# Power_Supply.net
KiCad netlist of a schematic drawn in Altium Designer
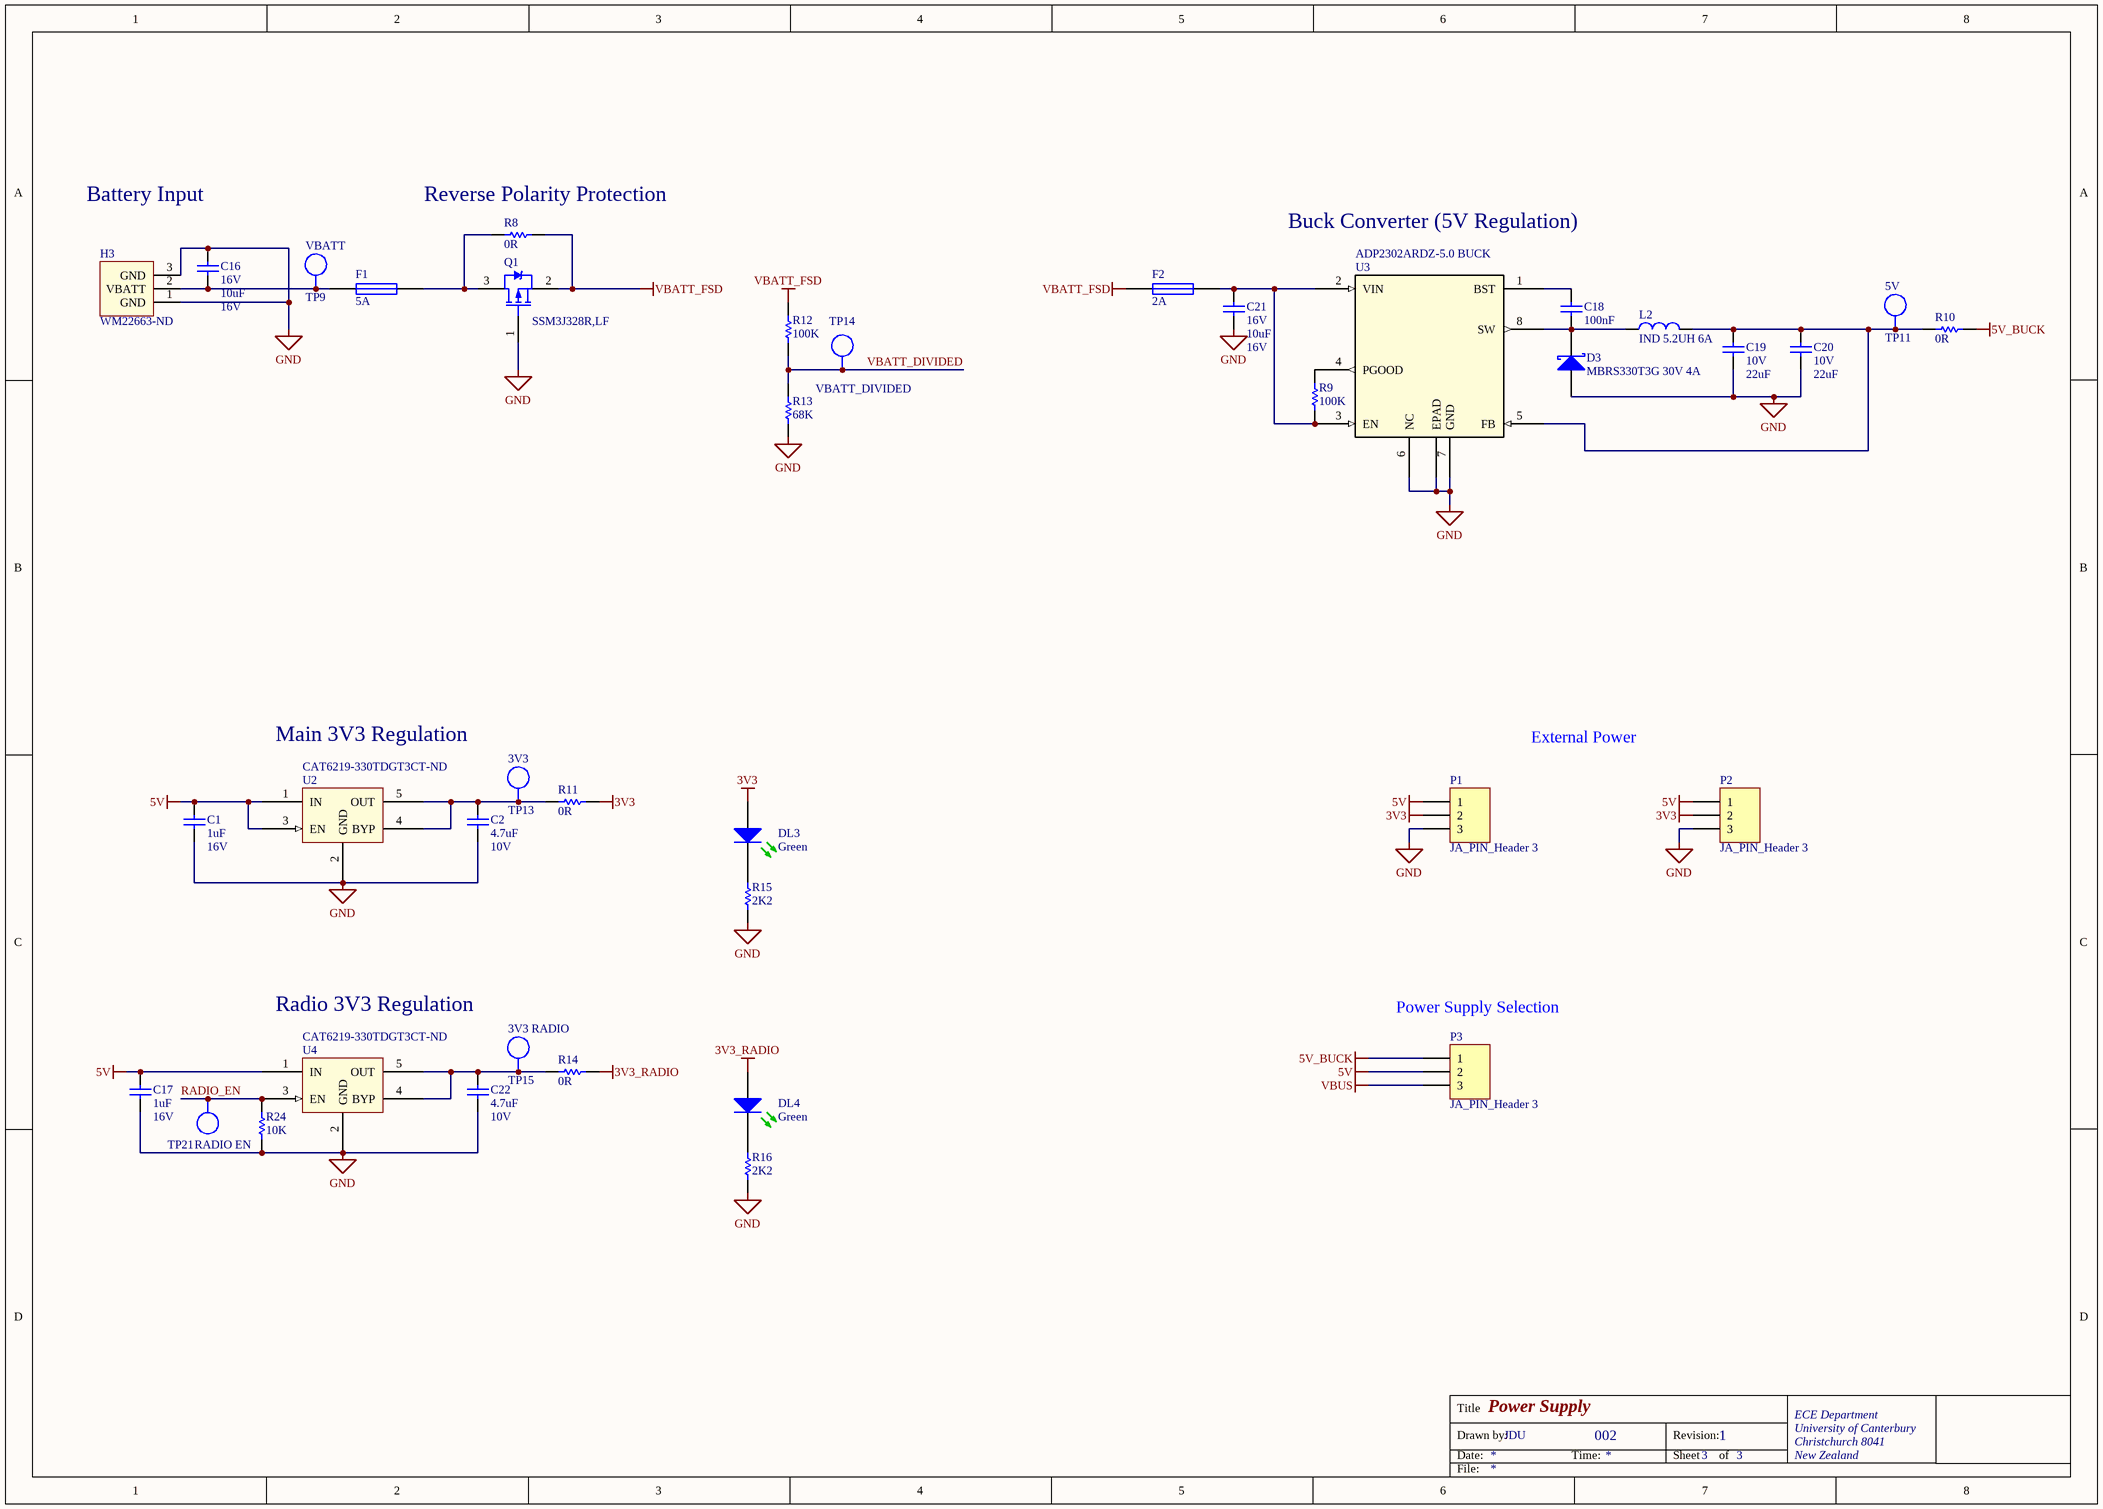
[diagram p0: Power_Supply.SchDoc]

(export (version "E")
  (design (tool "Eeschema 10.0.6"))
  (components
    (comp (ref "C1")
      (value "1uF")
      (footprint "CAPC1608L")
      (description "CAP CER 1uF Y5V -20% +80% 16V 0603")
      (fields (field (name "MAX VOLTAGE") "16V"))
      (libsource (lib "ECE_ComponentsAD23") (part "CC_1uF_0603"))
    )
    (comp (ref "C2")
      (value "4.7uF")
      (footprint "CAPC1608N")
      (description "CAP CER 4.7uF X5R +-20%  10V 0603")
      (fields (field (name "MAX VOLTAGE") "10V"))
      (libsource (lib "ECE_ComponentsAD23") (part "CC_4.7uF_0603"))
    )
    (comp (ref "C16")
      (value "10uF")
      (footprint "CAPC2012L")
      (description "CAP CER 10uF X5R 16V 0805")
      (fields
        (field (name "MANUFACTURER") "Samsung Electro-Mechanics")
        (field (name "MANUFACTURER PART NUMBER") "CL21A106KOQNNWE")
        (field (name "VOLTAGE - RATED") "16V")
        (field (name "MAX VOLTAGE") "16V")
      )
      (libsource (lib "ECE_ComponentsAD23") (part "CC_10uF_0805_16V"))
    )
    (comp (ref "C17")
      (value "1uF")
      (footprint "CAPC1608L")
      (description "CAP CER 1uF Y5V -20% +80% 16V 0603")
      (fields (field (name "MAX VOLTAGE") "16V"))
      (libsource (lib "ECE_ComponentsAD23") (part "CC_1uF_0603"))
    )
    (comp (ref "C18")
      (value "100nF")
      (footprint "CAPC1608L")
      (description "CAP CER 100nF X7R +-10% 50V 0603")
      (libsource (lib "ECE_ComponentsAD23") (part "CC_100nF_0603"))
    )
    (comp (ref "C19")
      (value "22uF")
      (footprint "CAPC3216L")
      (description "CAP CER 22uF Y5V -20% +80% 10V 1206")
      (fields (field (name "MAX VOLTAGE") "10V"))
      (libsource (lib "ECE_ComponentsAD23") (part "CC_22uF_1206"))
    )
    (comp (ref "C20")
      (value "22uF")
      (footprint "CAPC3216L")
      (description "CAP CER 22uF Y5V -20% +80% 10V 1206")
      (fields (field (name "MAX VOLTAGE") "10V"))
      (libsource (lib "ECE_ComponentsAD23") (part "CC_22uF_1206"))
    )
    (comp (ref "C21")
      (value "10uF")
      (footprint "CAPC2012L")
      (description "CAP CER 10uF X5R 16V 0805")
      (fields
        (field (name "MANUFACTURER") "Samsung Electro-Mechanics")
        (field (name "MANUFACTURER PART NUMBER") "CL21A106KOQNNWE")
        (field (name "VOLTAGE - RATED") "16V")
        (field (name "MAX VOLTAGE") "16V")
      )
      (libsource (lib "ECE_ComponentsAD23") (part "CC_10uF_0805_16V"))
    )
    (comp (ref "C22")
      (value "4.7uF")
      (footprint "CAPC1608N")
      (description "CAP CER 4.7uF X5R +-20%  10V 0603")
      (fields (field (name "MAX VOLTAGE") "10V"))
      (libsource (lib "ECE_ComponentsAD23") (part "CC_4.7uF_0603"))
    )
    (comp (ref "D3")
      (value "MBRS330T3G 30V 4A")
      (footprint "SMC")
      (description "SCHOTTKY  30V 4A")
      (fields
        (field (name "MANUFACTURER") "ON Semiconductor")
        (field (name "MANUFACTURER PART NUMBER") "MBRS330T3G")
      )
      (libsource (lib "ENCE461AD23") (part "MBRS330T3G"))
    )
    (comp (ref "DL3")
      (value "Green")
      (footprint "WL-SMCW0603")
      (description "LED Green 430mcd 0603 SMD")
      (fields
        (field (name "MANUFACTURER") "WURTH ELEKTRONIK")
        (field (name "MANUFACTURER PART NUMBER") "150060GS75000")
        (field (name "LED COLOUR") "Green")
      )
      (libsource (lib "ECE_ComponentsAD23") (part "DL_150060GS75000"))
    )
    (comp (ref "DL4")
      (value "Green")
      (footprint "WL-SMCW0603")
      (description "LED Green 430mcd 0603 SMD")
      (fields
        (field (name "MANUFACTURER") "WURTH ELEKTRONIK")
        (field (name "MANUFACTURER PART NUMBER") "150060GS75000")
        (field (name "LED COLOUR") "Green")
      )
      (libsource (lib "ECE_ComponentsAD23") (part "DL_150060GS75000"))
    )
    (comp (ref "F1")
      (value "5A")
      (footprint "RESC3216N")
      (description "Fuse 5.0A Fast Acting 1206 SMD")
      (fields (field (name "MANUFACTURER PART NUMBER") "C1F5") (field (name "MANUFACTURER") "Bel TRP"))
      (libsource (lib "ECE_ComponentsAD23") (part "FS_Fuse_5.0A"))
    )
    (comp (ref "F2")
      (value "2A")
      (footprint "RESC3216N")
      (description "Fuse 2.0A Very Fast Acting 1206 SMD")
      (fields
        (field (name "MANUFACTURER") "MULTICOMP")
        (field (name "MANUFACTURER PART NUMBER") "MC12CF 002")
      )
      (libsource (lib "ECE_ComponentsAD23") (part "FS_Fuse_2.0A"))
    )
    (comp (ref "H3")
      (value "Battery_HEADER_3pin")
      (footprint "BATT_HEADER_3POS")
      (description "3Pin Header 2.54mm spacing\r\nDigikey #WM22663-ND")
      (fields (field (name "SUPPLIER PART NUMBER 1") "WM22663-ND"))
      (libsource (lib "ENCE461AD23") (part "Battery_HEADER_3pin"))
    )
    (comp (ref "L2")
      (value "IND 5.2UH 6A")
      (footprint "INDUCTOR5u2")
      (description "FIXED IND 5.2UH 6A 22 MOHM SMD")
      (fields
        (field (name "MANUFACTURER") "Sumida America Components Inc.")
        (field (name "MANUFACTURER PART NUMBER") "CDRH104RNP-5R2NC")
      )
      (libsource (lib "ENCE461AD23") (part "CDRH104RNP-5R2NC"))
    )
    (comp (ref "P1")
      (value "JA_PIN_Header 3")
      (footprint "HDR1X3")
      (description "Header, 3-Pin")
      (fields (field (name "PUBLISHER") "Altium Limited"))
      (libsource (lib "ECE_ComponentsAD23") (part "JA_PIN_Header 3"))
    )
    (comp (ref "P2")
      (value "JA_PIN_Header 3")
      (footprint "HDR1X3")
      (description "Header, 3-Pin")
      (fields (field (name "PUBLISHER") "Altium Limited"))
      (libsource (lib "ECE_ComponentsAD23") (part "JA_PIN_Header 3"))
    )
    (comp (ref "P3")
      (value "JA_PIN_Header 3")
      (footprint "HDR1X3")
      (description "Header, 3-Pin")
      (fields (field (name "PUBLISHER") "Altium Limited"))
      (libsource (lib "ECE_ComponentsAD23") (part "JA_PIN_Header 3"))
    )
    (comp (ref "Q1")
      (value "SSM3J328R,LF")
      (footprint "SOT23_L")
      (description "MOSFET P-CH 20V 6A SOT23-3")
      (fields
        (field (name "MANUFACTURER") "Toshiba")
        (field (name "MANUFACTURER PART NUMBER") "SSM3J328R,LF")
      )
      (libsource (lib "ECE_ComponentsAD23") (part "TM_SSM3J328R"))
    )
    (comp (ref "R8")
      (value "0R")
      (footprint "RESC1608L")
      (description "RES 0.0 OHM 1/10W 5% 0603 SMD")
      (libsource (lib "ECE_ComponentsAD23") (part "RS_0R0"))
    )
    (comp (ref "R9")
      (value "100K")
      (footprint "RESC1608L")
      (description "RES 100K OHM 1/10W 5% 0603 SMD")
      (libsource (lib "ECE_ComponentsAD23") (part "RS_100K"))
    )
    (comp (ref "R10")
      (value "0R")
      (footprint "RESC1608L")
      (description "RES 0.0 OHM 1/10W 5% 0603 SMD")
      (libsource (lib "ECE_ComponentsAD23") (part "RS_0R0"))
    )
    (comp (ref "R11")
      (value "0R")
      (footprint "RESC1608L")
      (description "RES 0.0 OHM 1/10W 5% 0603 SMD")
      (libsource (lib "ECE_ComponentsAD23") (part "RS_0R0"))
    )
    (comp (ref "R12")
      (value "100K")
      (footprint "RESC1608L")
      (description "RES 100K OHM 1/10W 5% 0603 SMD")
      (libsource (lib "ECE_ComponentsAD23") (part "RS_100K"))
    )
    (comp (ref "R13")
      (value "68K")
      (footprint "RESC1608L")
      (description "RES 68.0K OHM 1/10W 5% 0603 SMD")
      (libsource (lib "ECE_ComponentsAD23") (part "RS_68K"))
    )
    (comp (ref "R14")
      (value "0R")
      (footprint "RESC1608L")
      (description "RES 0.0 OHM 1/10W 5% 0603 SMD")
      (libsource (lib "ECE_ComponentsAD23") (part "RS_0R0"))
    )
    (comp (ref "R15")
      (value "2K2")
      (footprint "RESC1608L")
      (description "RES 2.2K OHM 1/10W 5% 0603 SMD")
      (libsource (lib "ECE_ComponentsAD23") (part "RS_2K2"))
    )
    (comp (ref "R16")
      (value "2K2")
      (footprint "RESC1608L")
      (description "RES 2.2K OHM 1/10W 5% 0603 SMD")
      (libsource (lib "ECE_ComponentsAD23") (part "RS_2K2"))
    )
    (comp (ref "R24")
      (value "10K")
      (footprint "RESC1608L")
      (description "RES 10.0K OHM 1/10W 5% 0603 SMD")
      (libsource (lib "ECE_ComponentsAD23") (part "RS_10K"))
    )
    (comp (ref "TP9")
      (value "VBATT")
      (footprint "TP_1206")
      (description "Test-Point 3.3x1.6x2.1mm SMD")
      (fields
        (field (name "MANUFACTURER") "Harwin Inc")
        (field (name "MANUFACTURER PART NUMBER") "S1751-46R")
      )
      (libsource (lib "ECE_ComponentsAD23") (part "TP_1206"))
    )
    (comp (ref "TP11")
      (value "5V")
      (footprint "TP_1206")
      (description "Test-Point 3.3x1.6x2.1mm SMD")
      (fields
        (field (name "MANUFACTURER") "Harwin Inc")
        (field (name "MANUFACTURER PART NUMBER") "S1751-46R")
      )
      (libsource (lib "ECE_ComponentsAD23") (part "TP_1206"))
    )
    (comp (ref "TP13")
      (value "3V3")
      (footprint "TP_1206")
      (description "Test-Point 3.3x1.6x2.1mm SMD")
      (fields
        (field (name "MANUFACTURER") "Harwin Inc")
        (field (name "MANUFACTURER PART NUMBER") "S1751-46R")
      )
      (libsource (lib "ECE_ComponentsAD23") (part "TP_1206"))
    )
    (comp (ref "TP14")
      (value "VBATT_DIVIDED")
      (footprint "TP_1206")
      (description "Test-Point 3.3x1.6x2.1mm SMD")
      (fields
        (field (name "MANUFACTURER") "Harwin Inc")
        (field (name "MANUFACTURER PART NUMBER") "S1751-46R")
      )
      (libsource (lib "ECE_ComponentsAD23") (part "TP_1206"))
    )
    (comp (ref "TP15")
      (value "3V3 RADIO")
      (footprint "TP_1206")
      (description "Test-Point 3.3x1.6x2.1mm SMD")
      (fields
        (field (name "MANUFACTURER") "Harwin Inc")
        (field (name "MANUFACTURER PART NUMBER") "S1751-46R")
      )
      (libsource (lib "ECE_ComponentsAD23") (part "TP_1206"))
    )
    (comp (ref "TP21")
      (value "RADIO EN")
      (footprint "TP_1206")
      (description "Test-Point 3.3x1.6x2.1mm SMD")
      (fields
        (field (name "MANUFACTURER") "Harwin Inc")
        (field (name "MANUFACTURER PART NUMBER") "S1751-46R")
      )
      (libsource (lib "ECE_ComponentsAD23") (part "TP_1206"))
    )
    (comp (ref "U2")
      (value "CAT6219-330TDGT3")
      (footprint "SOT95P280X145-5N")
      (description "IC REG LIN 3.3V 500MA TSOT23-5")
      (fields
        (field (name "BASE PART NUMBER") "CAT6219")
        (field (name "SUPPLIER PART NUMBER") "CAT6219-330TDGT3CT-ND")
      )
      (libsource (lib "ENCE461AD23") (part "SV_CAT6219-330TDGT3"))
    )
    (comp (ref "U3")
      (value "ADP2302ARDZ-5.0 BUCK")
      (footprint "RD_8_1")
      (description "IC REG BUCK 5V 2A 8SOIC")
      (fields (field (name "MANUFACTURER_PART_NUMBER") "ADP2302ARDZ-5.0-R7"))
      (libsource (lib "ENCE461AD23") (part "ADP2302ARDZ-5.0-R7"))
    )
    (comp (ref "U4")
      (value "CAT6219-330TDGT3")
      (footprint "SOT95P280X145-5N")
      (description "IC REG LIN 3.3V 500MA TSOT23-5")
      (fields
        (field (name "BASE PART NUMBER") "CAT6219")
        (field (name "SUPPLIER PART NUMBER") "CAT6219-330TDGT3CT-ND")
      )
      (libsource (lib "ENCE461AD23") (part "SV_CAT6219-330TDGT3"))
    )
  )
  (nets
    (net (code "1") (name "/RADIO_EN") (class "Default")
      (node (ref "R24") (pin "2") (pinfunction "2_2") (pintype "passive"))
      (node (ref "TP21") (pin "1") (pinfunction "1_1") (pintype "passive"))
      (node (ref "U4") (pin "3") (pinfunction "EN_3") (pintype "input"))
    )
    (net (code "2") (name "/VBATT_DIVIDED") (class "Default")
      (node (ref "R12") (pin "1") (pinfunction "1_1") (pintype "passive"))
      (node (ref "R13") (pin "2") (pinfunction "2_2") (pintype "passive"))
      (node (ref "TP14") (pin "1") (pinfunction "1_1") (pintype "passive"))
    )
    (net (code "3") (name "3V3") (class "Default")
      (node (ref "DL3") (pin "2") (pinfunction "A_2") (pintype "passive"))
      (node (ref "P1") (pin "2") (pinfunction "2_2") (pintype "passive"))
      (node (ref "P2") (pin "2") (pinfunction "2_2") (pintype "passive"))
      (node (ref "R11") (pin "2") (pinfunction "2_2") (pintype "passive"))
    )
    (net (code "4") (name "3V3_RADIO") (class "Default")
      (node (ref "DL4") (pin "2") (pinfunction "A_2") (pintype "passive"))
      (node (ref "R14") (pin "2") (pinfunction "2_2") (pintype "passive"))
    )
    (net (code "5") (name "5V") (class "Default")
      (node (ref "C1") (pin "1") (pinfunction "1_1") (pintype "passive"))
      (node (ref "C17") (pin "1") (pinfunction "1_1") (pintype "passive"))
      (node (ref "P1") (pin "1") (pinfunction "1_1") (pintype "passive"))
      (node (ref "P2") (pin "1") (pinfunction "1_1") (pintype "passive"))
      (node (ref "P3") (pin "2") (pinfunction "2_2") (pintype "passive"))
      (node (ref "U2") (pin "1") (pinfunction "IN_1") (pintype "power_in"))
      (node (ref "U2") (pin "3") (pinfunction "EN_3") (pintype "input"))
      (node (ref "U4") (pin "1") (pinfunction "IN_1") (pintype "power_in"))
    )
    (net (code "6") (name "5V_BUCK") (class "Default")
      (node (ref "P3") (pin "1") (pinfunction "1_1") (pintype "passive"))
      (node (ref "R10") (pin "2") (pinfunction "2_2") (pintype "passive"))
    )
    (net (code "7") (name "GND") (class "Default")
      (node (ref "C1") (pin "2") (pinfunction "2_2") (pintype "passive"))
      (node (ref "C16") (pin "2") (pinfunction "2_2") (pintype "passive"))
      (node (ref "C17") (pin "2") (pinfunction "2_2") (pintype "passive"))
      (node (ref "C19") (pin "1") (pinfunction "1_1") (pintype "passive"))
      (node (ref "C2") (pin "1") (pinfunction "1_1") (pintype "passive"))
      (node (ref "C20") (pin "1") (pinfunction "1_1") (pintype "passive"))
      (node (ref "C21") (pin "1") (pinfunction "1_1") (pintype "passive"))
      (node (ref "C22") (pin "1") (pinfunction "1_1") (pintype "passive"))
      (node (ref "D3") (pin "1") (pinfunction "A_1") (pintype "passive"))
      (node (ref "H3") (pin "1") (pinfunction "GND_1") (pintype "passive"))
      (node (ref "H3") (pin "3") (pinfunction "GND_3") (pintype "passive"))
      (node (ref "P1") (pin "3") (pinfunction "3_3") (pintype "passive"))
      (node (ref "P2") (pin "3") (pinfunction "3_3") (pintype "passive"))
      (node (ref "Q1") (pin "1") (pinfunction "1_1") (pintype "passive"))
      (node (ref "R13") (pin "1") (pinfunction "1_1") (pintype "passive"))
      (node (ref "R15") (pin "1") (pinfunction "1_1") (pintype "passive"))
      (node (ref "R16") (pin "1") (pinfunction "1_1") (pintype "passive"))
      (node (ref "R24") (pin "1") (pinfunction "1_1") (pintype "passive"))
      (node (ref "U2") (pin "2") (pinfunction "GND_2") (pintype "power_in"))
      (node (ref "U3") (pin "6") (pinfunction "NC_6") (pintype "passive"))
      (node (ref "U3") (pin "7") (pinfunction "GND_7") (pintype "power_in"))
      (node (ref "U3") (pin "EPAD") (pinfunction "EPAD_EPAD") (pintype "passive"))
      (node (ref "U4") (pin "2") (pinfunction "GND_2") (pintype "power_in"))
    )
    (net (code "8") (name "Net-(D3-K)") (class "Default")
      (node (ref "C18") (pin "1") (pinfunction "1_1") (pintype "passive"))
      (node (ref "D3") (pin "2") (pinfunction "K_2") (pintype "passive"))
      (node (ref "L2") (pin "1") (pintype "passive"))
      (node (ref "U3") (pin "8") (pinfunction "SW_8") (pintype "output"))
    )
    (net (code "9") (name "Net-(DL3-K)") (class "Default")
      (node (ref "DL3") (pin "1") (pinfunction "K_1") (pintype "passive"))
      (node (ref "R15") (pin "2") (pinfunction "2_2") (pintype "passive"))
    )
    (net (code "10") (name "Net-(DL4-K)") (class "Default")
      (node (ref "DL4") (pin "1") (pinfunction "K_1") (pintype "passive"))
      (node (ref "R16") (pin "2") (pinfunction "2_2") (pintype "passive"))
    )
    (net (code "11") (name "Net-(F1-Pad2)") (class "Default")
      (node (ref "F1") (pin "2") (pinfunction "2_2") (pintype "passive"))
      (node (ref "Q1") (pin "3") (pinfunction "3_3") (pintype "passive"))
      (node (ref "R8") (pin "1") (pinfunction "1_1") (pintype "passive"))
    )
    (net (code "12") (name "Net-(H3-VBATT)") (class "Default")
      (node (ref "C16") (pin "1") (pinfunction "1_1") (pintype "passive"))
      (node (ref "F1") (pin "1") (pinfunction "1_1") (pintype "passive"))
      (node (ref "H3") (pin "2") (pinfunction "VBATT_2") (pintype "passive"))
      (node (ref "TP9") (pin "1") (pinfunction "1_1") (pintype "passive"))
    )
    (net (code "13") (name "Net-(U2-BYP)") (class "Default")
      (node (ref "C2") (pin "2") (pinfunction "2_2") (pintype "passive"))
      (node (ref "R11") (pin "1") (pinfunction "1_1") (pintype "passive"))
      (node (ref "TP13") (pin "1") (pinfunction "1_1") (pintype "passive"))
      (node (ref "U2") (pin "4") (pinfunction "BYP_4") (pintype "passive"))
      (node (ref "U2") (pin "5") (pinfunction "OUT_5") (pintype "power_in"))
    )
    (net (code "14") (name "Net-(U3-BST)") (class "Default")
      (node (ref "C18") (pin "2") (pinfunction "2_2") (pintype "passive"))
      (node (ref "U3") (pin "1") (pinfunction "BST_1") (pintype "passive"))
    )
    (net (code "15") (name "Net-(U3-EN)") (class "Default")
      (node (ref "C21") (pin "2") (pinfunction "2_2") (pintype "passive"))
      (node (ref "F2") (pin "2") (pinfunction "2_2") (pintype "passive"))
      (node (ref "R9") (pin "1") (pinfunction "1_1") (pintype "passive"))
      (node (ref "U3") (pin "2") (pinfunction "VIN_2") (pintype "input"))
      (node (ref "U3") (pin "3") (pinfunction "EN_3") (pintype "input"))
    )
    (net (code "16") (name "Net-(U3-FB)") (class "Default")
      (node (ref "C19") (pin "2") (pinfunction "2_2") (pintype "passive"))
      (node (ref "C20") (pin "2") (pinfunction "2_2") (pintype "passive"))
      (node (ref "L2") (pin "2") (pintype "passive"))
      (node (ref "R10") (pin "1") (pinfunction "1_1") (pintype "passive"))
      (node (ref "TP11") (pin "1") (pinfunction "1_1") (pintype "passive"))
      (node (ref "U3") (pin "5") (pinfunction "FB_5") (pintype "input"))
    )
    (net (code "17") (name "Net-(U3-PGOOD)") (class "Default")
      (node (ref "R9") (pin "2") (pinfunction "2_2") (pintype "passive"))
      (node (ref "U3") (pin "4") (pinfunction "PGOOD_4") (pintype "output"))
    )
    (net (code "18") (name "Net-(U4-BYP)") (class "Default")
      (node (ref "C22") (pin "2") (pinfunction "2_2") (pintype "passive"))
      (node (ref "R14") (pin "1") (pinfunction "1_1") (pintype "passive"))
      (node (ref "TP15") (pin "1") (pinfunction "1_1") (pintype "passive"))
      (node (ref "U4") (pin "4") (pinfunction "BYP_4") (pintype "passive"))
      (node (ref "U4") (pin "5") (pinfunction "OUT_5") (pintype "power_in"))
    )
    (net (code "19") (name "VBATT_FSD") (class "Default")
      (node (ref "F2") (pin "1") (pinfunction "1_1") (pintype "passive"))
      (node (ref "Q1") (pin "2") (pinfunction "2_2") (pintype "passive"))
      (node (ref "R12") (pin "2") (pinfunction "2_2") (pintype "passive"))
      (node (ref "R8") (pin "2") (pinfunction "2_2") (pintype "passive"))
    )
    (net (code "20") (name "VBUS") (class "Default")
      (node (ref "P3") (pin "3") (pinfunction "3_3") (pintype "passive"))
    )
  )
)
